# Power.net
KiCad netlist of a schematic drawn in Altium Designer
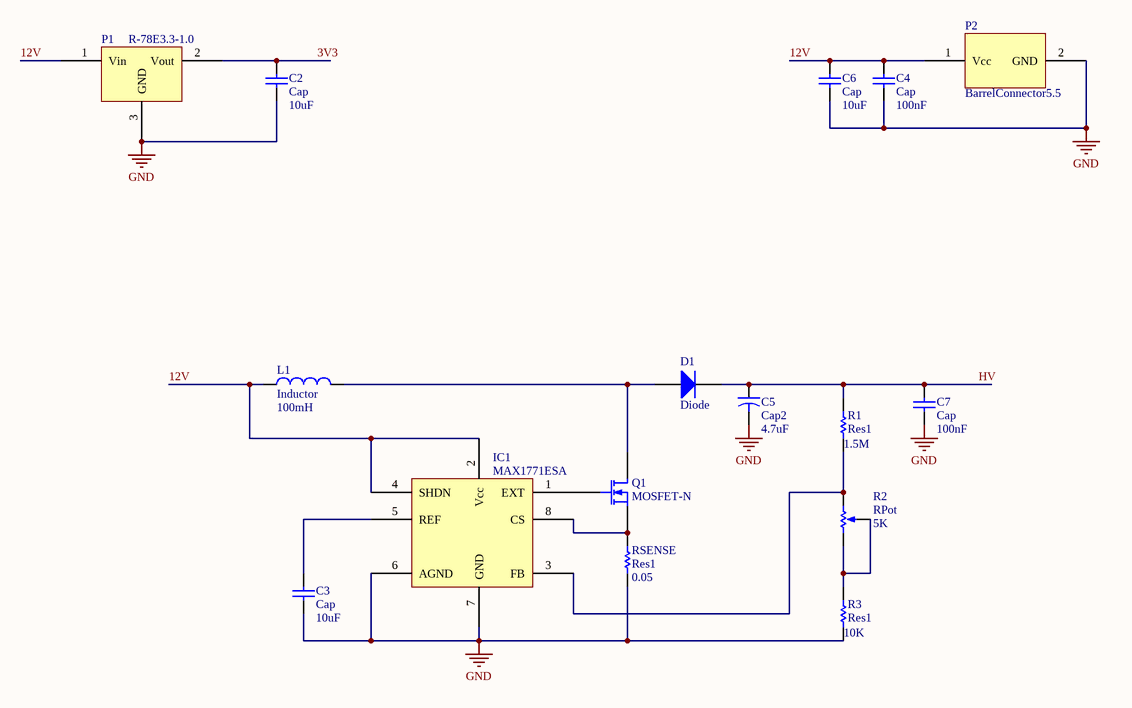
[diagram p0: Power.SchDoc]

(export (version "E")
  (design (tool "Eeschema 10.0.6"))
  (components
    (comp (ref "C2")
      (value "Cap")
      (footprint "6-0805_M")
      (description "Capacitor")
      (fields (field (name "ALTIUM_VALUE") "10uF") (field (name "PUBLISHER") "Altium Limited"))
      (libsource (lib "Miscellaneous Devices") (part "Cap"))
    )
    (comp (ref "C3")
      (value "Cap")
      (footprint "6-0805_M")
      (description "Capacitor")
      (fields (field (name "ALTIUM_VALUE") "10uF") (field (name "PUBLISHER") "Altium Limited"))
      (libsource (lib "Miscellaneous Devices") (part "Cap"))
    )
    (comp (ref "C4")
      (value "Cap")
      (footprint "6-0805_M")
      (description "Capacitor")
      (fields (field (name "ALTIUM_VALUE") "100nF") (field (name "PUBLISHER") "Altium Limited"))
      (libsource (lib "Miscellaneous Devices") (part "Cap"))
    )
    (comp (ref "C5")
      (value "Cap2")
      (footprint "G17")
      (description "Capacitor")
      (fields (field (name "ALTIUM_VALUE") "4.7uF") (field (name "PUBLISHER") "Altium Limited"))
      (libsource (lib "Miscellaneous Devices") (part "Cap2"))
    )
    (comp (ref "C6")
      (value "Cap")
      (footprint "6-0805_M")
      (description "Capacitor")
      (fields (field (name "ALTIUM_VALUE") "10uF") (field (name "PUBLISHER") "Altium Limited"))
      (libsource (lib "Miscellaneous Devices") (part "Cap"))
    )
    (comp (ref "C7")
      (value "Cap")
      (footprint "Cap2420")
      (description "Capacitor")
      (fields (field (name "ALTIUM_VALUE") "100nF") (field (name "PUBLISHER") "Altium Limited"))
      (libsource (lib "Miscellaneous Devices") (part "Cap"))
    )
    (comp (ref "D1")
      (value "Diode")
      (footprint "DO-214AA")
      (description "Default Diode")
      (fields (field (name "PUBLISHER") "Altium Limited"))
      (libsource (lib "Miscellaneous Devices") (part "Diode"))
    )
    (comp (ref "IC1")
      (value "MAX1771ESA")
      (footprint "SOIC-8(1.27mm)")
      (libsource (lib "CustomComponentsLibrary") (part "MAX1771ESA"))
    )
    (comp (ref "L1")
      (value "Inductor")
      (footprint "SMDInductor")
      (fields (field (name "ALTIUM_VALUE") "100mH") (field (name "PUBLISHER") "Altium Limited"))
      (libsource (lib "Miscellaneous Devices") (part "Inductor"))
    )
    (comp (ref "P1")
      (value "R-78E3.3-1.0")
      (footprint "R-78E3.3-1.0")
      (libsource (lib "CustomComponentsLibrary") (part "R-78E3.3-1.0"))
    )
    (comp (ref "P2")
      (value "BarrelConnector5.5")
      (footprint "BarrelConnector5.5")
      (libsource (lib "CustomComponentsLibrary") (part "BarrelConnector5.5"))
    )
    (comp (ref "Q1")
      (value "MOSFET-N")
      (footprint "TO-220-AB")
      (description "N-Channel MOSFET")
      (fields (field (name "PUBLISHER") "Altium Limited"))
      (libsource (lib "Miscellaneous Devices") (part "MOSFET-N"))
    )
    (comp (ref "R1")
      (value "Res1")
      (footprint "Res2512")
      (description "Resistor")
      (fields (field (name "ALTIUM_VALUE") "1.5M") (field (name "PUBLISHER") "Altium Limited"))
      (libsource (lib "Miscellaneous Devices") (part "Res1"))
    )
    (comp (ref "R2")
      (value "RPot")
      (footprint "PVG3G")
      (description "Potentiometer")
      (fields (field (name "ALTIUM_VALUE") "5K") (field (name "PUBLISHER") "Altium Limited"))
      (libsource (lib "Miscellaneous Devices") (part "RPot"))
    )
    (comp (ref "R3")
      (value "Res1")
      (footprint "6-0805_M")
      (description "Resistor")
      (fields (field (name "ALTIUM_VALUE") "10K") (field (name "PUBLISHER") "Altium Limited"))
      (libsource (lib "Miscellaneous Devices") (part "Res1"))
    )
    (comp (ref "RSENSE")
      (value "Res1")
      (footprint "Res2512")
      (description "Resistor")
      (fields (field (name "ALTIUM_VALUE") "0.05") (field (name "PUBLISHER") "Altium Limited"))
      (libsource (lib "Miscellaneous Devices") (part "Res1"))
    )
  )
  (nets
    (net (code "1") (name "/3V3") (class "Default")
      (node (ref "C2") (pin "2") (pinfunction "2_2") (pintype "passive"))
      (node (ref "P1") (pin "2") (pinfunction "Vout_2") (pintype "passive"))
    )
    (net (code "2") (name "/12V") (class "Default")
      (node (ref "C4") (pin "2") (pinfunction "2_2") (pintype "passive"))
      (node (ref "C6") (pin "2") (pinfunction "2_2") (pintype "passive"))
      (node (ref "IC1") (pin "2") (pinfunction "Vcc_2") (pintype "passive"))
      (node (ref "IC1") (pin "4") (pinfunction "SHDN_4") (pintype "passive"))
      (node (ref "L1") (pin "1") (pinfunction "1_1") (pintype "passive"))
      (node (ref "P1") (pin "1") (pinfunction "Vin_1") (pintype "passive"))
      (node (ref "P2") (pin "1") (pinfunction "Vcc_1") (pintype "passive"))
    )
    (net (code "3") (name "/HV") (class "Default")
      (node (ref "C5") (pin "1") (pinfunction "1_1") (pintype "passive"))
      (node (ref "C7") (pin "2") (pinfunction "2_2") (pintype "passive"))
      (node (ref "D1") (pin "2") (pinfunction "K_2") (pintype "passive"))
      (node (ref "R1") (pin "2") (pinfunction "2_2") (pintype "passive"))
    )
    (net (code "4") (name "GND") (class "Default")
      (node (ref "C2") (pin "1") (pinfunction "1_1") (pintype "passive"))
      (node (ref "C3") (pin "1") (pinfunction "1_1") (pintype "passive"))
      (node (ref "C4") (pin "1") (pinfunction "1_1") (pintype "passive"))
      (node (ref "C5") (pin "2") (pinfunction "2_2") (pintype "passive"))
      (node (ref "C6") (pin "1") (pinfunction "1_1") (pintype "passive"))
      (node (ref "C7") (pin "1") (pinfunction "1_1") (pintype "passive"))
      (node (ref "IC1") (pin "6") (pinfunction "AGND_6") (pintype "passive"))
      (node (ref "IC1") (pin "7") (pinfunction "GND_7") (pintype "passive"))
      (node (ref "P1") (pin "3") (pinfunction "GND_3") (pintype "passive"))
      (node (ref "P2") (pin "2") (pinfunction "GND_2") (pintype "passive"))
      (node (ref "R3") (pin "1") (pinfunction "1_1") (pintype "passive"))
      (node (ref "RSENSE") (pin "1") (pinfunction "1_1") (pintype "passive"))
    )
    (net (code "5") (name "Net-(D1-A)") (class "Default")
      (node (ref "D1") (pin "1") (pinfunction "A_1") (pintype "passive"))
      (node (ref "L1") (pin "2") (pinfunction "2_2") (pintype "passive"))
      (node (ref "Q1") (pin "1") (pinfunction "D_1") (pintype "passive"))
    )
    (net (code "6") (name "Net-(IC1-CS)") (class "Default")
      (node (ref "IC1") (pin "8") (pinfunction "CS_8") (pintype "passive"))
      (node (ref "Q1") (pin "3") (pinfunction "S_3") (pintype "passive"))
      (node (ref "RSENSE") (pin "2") (pinfunction "2_2") (pintype "passive"))
    )
    (net (code "7") (name "Net-(IC1-EXT)") (class "Default")
      (node (ref "IC1") (pin "1") (pinfunction "EXT_1") (pintype "passive"))
      (node (ref "Q1") (pin "2") (pinfunction "G_2") (pintype "passive"))
    )
    (net (code "8") (name "Net-(IC1-FB)") (class "Default")
      (node (ref "IC1") (pin "3") (pinfunction "FB_3") (pintype "passive"))
      (node (ref "R1") (pin "1") (pinfunction "1_1") (pintype "passive"))
      (node (ref "R2") (pin "2") (pinfunction "BOT_2") (pintype "passive"))
    )
    (net (code "9") (name "Net-(IC1-REF)") (class "Default")
      (node (ref "C3") (pin "2") (pinfunction "2_2") (pintype "passive"))
      (node (ref "IC1") (pin "5") (pinfunction "REF_5") (pintype "passive"))
    )
    (net (code "10") (name "Net-(R2-TAP)") (class "Default")
      (node (ref "R2") (pin "1") (pinfunction "TOP_1") (pintype "passive"))
      (node (ref "R2") (pin "3") (pinfunction "TAP_3") (pintype "passive"))
      (node (ref "R3") (pin "2") (pinfunction "2_2") (pintype "passive"))
    )
  )
)
